# v1_1.net
KiCad netlist of a schematic drawn in Altium Designer
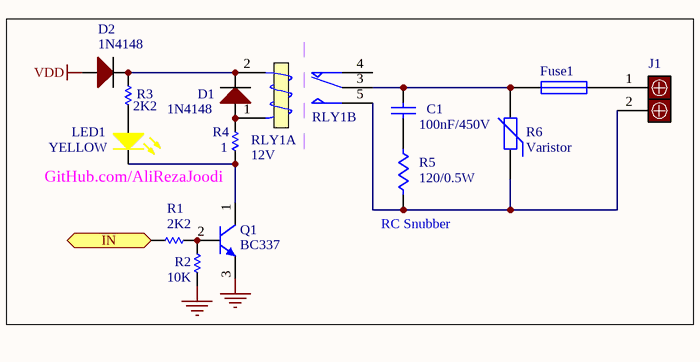
[diagram p0: v1.1.SchDoc]

(export (version "E")
  (design (tool "Eeschema 10.0.6"))
  (components
    (comp (ref "C1")
      (value "100nF/450V")
      (footprint "C_THD_CER_(P2.54-D3.5-T1.5)")
      (description "Capacitor, Ceramic Multilayer")
      (libsource (lib "Passive") (part "Capacitor_Ceramic"))
    )
    (comp (ref "D1")
      (value "1N4148")
      (footprint "D_THD_AXIAL0.3_DO-35")
      (description "Diode,")
      (libsource (lib "Passive") (part "Diode_2Form"))
    )
    (comp (ref "D2")
      (value "1N4148")
      (footprint "D_THD_AXIAL0.3_DO-35")
      (description "Diode,")
      (libsource (lib "Passive") (part "Diode_2Form"))
    )
    (comp (ref "Fuse1")
      (value "2A")
      (footprint "PIN-W2/E2.8")
      (description "Fuse")
      (fields (field (name "MANUFACTURER") "Generic Components") (field (name "PUBLISHER") "Altium Limited"))
      (libsource (lib "Miscellaneous Devices") (part "Fuse 1"))
    )
    (comp (ref "J1")
      (value "2PIN")
      (footprint "Connector_Phoenix_2PIN_MSTB")
      (description "Connector, Header, 2Pin")
      (libsource (lib "Connector") (part "Connector1x2_Power"))
    )
    (comp (ref "LED1")
      (value "YELLOW")
      (footprint "LED_THD_3MM_YELLOW_R")
      (description "LED, Yellow")
      (fields (field (name "MANUFACTURER") "Generic Components") (field (name "PUBLISHER") "Altium Limited"))
      (libsource (lib "Display") (part "LED_YELLOW"))
    )
    (comp (ref "Q1")
      (value "BC337")
      (footprint "TO92C")
      (description "NPN Bipolar Transistor")
      (fields (field (name "MANUFACTURER") "Generic Components") (field (name "PUBLISHER") "Altium Limited"))
      (libsource (lib "Miscellaneous Devices") (part "NPN"))
    )
    (comp (ref "R1")
      (value "2K2")
      (footprint "R_THD_AXIAL0.4(1/4W)")
      (description "Resistor")
      (libsource (lib "Passive") (part "Resistor"))
    )
    (comp (ref "R2")
      (value "10K")
      (footprint "R_THD_AXIAL0.4(1/4W)")
      (description "Resistor")
      (libsource (lib "Passive") (part "Resistor"))
    )
    (comp (ref "R3")
      (value "2K2")
      (footprint "R_THD_AXIAL0.4(1/4W)")
      (description "Resistor")
      (libsource (lib "Passive") (part "Resistor"))
    )
    (comp (ref "R4")
      (value "1")
      (footprint "R_THD_AXIAL0.4(1/4W)")
      (description "Resistor")
      (libsource (lib "Passive") (part "Resistor"))
    )
    (comp (ref "R5")
      (value "120/0.5W")
      (footprint "R_THD_AXIAL0.9(3W)")
      (description "Resistor")
      (libsource (lib "Passive") (part "Resistor_3Form"))
    )
    (comp (ref "R6")
      (value "Varistor")
      (footprint "R2012-0805")
      (description "Varistor (Voltage-Sensitive Resistor)")
      (fields (field (name "MANUFACTURER") "Generic Components") (field (name "PUBLISHER") "Altium Limited"))
      (libsource (lib "Miscellaneous Devices") (part "Res Varistor"))
    )
    (comp (ref "RLY1")
      (value "12V")
      (footprint "RELAY_SPDT_5PIN_2216")
      (description "SPDT Relay")
      (libsource (lib "Passive") (part "Relay_SPDT_2Form"))
    )
  )
  (nets
    (net (code "1") (name "/IN") (class "Default")
      (node (ref "R1") (pin "2") (pinfunction "2_2") (pintype "passive"))
    )
    (net (code "2") (name "GND") (class "Default")
      (node (ref "Q1") (pin "3") (pinfunction "E_3") (pintype "passive"))
      (node (ref "R2") (pin "1") (pinfunction "1_1") (pintype "passive"))
    )
    (net (code "3") (name "Net-(C1-Pad1)") (class "Default")
      (node (ref "C1") (pin "1") (pinfunction "1_1") (pintype "passive"))
      (node (ref "R5") (pin "2") (pinfunction "2_2") (pintype "passive"))
    )
    (net (code "4") (name "Net-(D1-A)") (class "Default")
      (node (ref "D1") (pin "1") (pinfunction "A_1") (pintype "passive"))
      (node (ref "R4") (pin "2") (pinfunction "2_2") (pintype "passive"))
      (node (ref "RLY1") (pin "1") (pinfunction "T2_1") (pintype "passive"))
    )
    (net (code "5") (name "Net-(D1-K)") (class "Default")
      (node (ref "D1") (pin "2") (pinfunction "K_2") (pintype "passive"))
      (node (ref "D2") (pin "2") (pinfunction "K_2") (pintype "passive"))
      (node (ref "R3") (pin "2") (pinfunction "2_2") (pintype "passive"))
      (node (ref "RLY1") (pin "2") (pinfunction "T1_2") (pintype "passive"))
    )
    (net (code "6") (name "Net-(Fuse1-Pad2)") (class "Default")
      (node (ref "Fuse1") (pin "2") (pinfunction "2_2") (pintype "passive"))
      (node (ref "J1") (pin "1") (pinfunction "1_1") (pintype "passive"))
    )
    (net (code "7") (name "Net-(LED1-A)") (class "Default")
      (node (ref "LED1") (pin "1") (pinfunction "A_1") (pintype "passive"))
      (node (ref "R3") (pin "1") (pinfunction "1_1") (pintype "passive"))
    )
    (net (code "8") (name "Net-(LED1-K)") (class "Default")
      (node (ref "LED1") (pin "2") (pinfunction "K_2") (pintype "passive"))
      (node (ref "Q1") (pin "1") (pinfunction "C_1") (pintype "passive"))
      (node (ref "R4") (pin "1") (pinfunction "1_1") (pintype "passive"))
    )
    (net (code "9") (name "Net-(Q1-B)") (class "Default")
      (node (ref "Q1") (pin "2") (pinfunction "B_2") (pintype "passive"))
      (node (ref "R1") (pin "1") (pinfunction "1_1") (pintype "passive"))
      (node (ref "R2") (pin "2") (pinfunction "2_2") (pintype "passive"))
    )
    (net (code "10") (name "Net-(RLY1B-COM)") (class "Default")
      (node (ref "C1") (pin "2") (pinfunction "2_2") (pintype "passive"))
      (node (ref "Fuse1") (pin "1") (pinfunction "1_1") (pintype "passive"))
      (node (ref "R6") (pin "2") (pinfunction "2_2") (pintype "passive"))
      (node (ref "RLY1") (pin "3") (pinfunction "COM_3") (pintype "passive"))
    )
    (net (code "11") (name "Net-(RLY1B-NO)") (class "Default")
      (node (ref "J1") (pin "2") (pinfunction "2_2") (pintype "passive"))
      (node (ref "R5") (pin "1") (pinfunction "1_1") (pintype "passive"))
      (node (ref "R6") (pin "1") (pinfunction "1_1") (pintype "passive"))
      (node (ref "RLY1") (pin "5") (pinfunction "NO_5") (pintype "passive"))
    )
    (net (code "12") (name "VDD") (class "Default")
      (node (ref "D2") (pin "1") (pinfunction "A_1") (pintype "passive"))
    )
    (net (code "13") (name "unconnected-(RLY1B-NC-Pad4)") (class "Default")
      (node (ref "RLY1") (pin "4") (pinfunction "NC_4") (pintype "passive"))
    )
  )
)
